# USB_HUB.net
KiCad netlist of a schematic drawn in Altium Designer
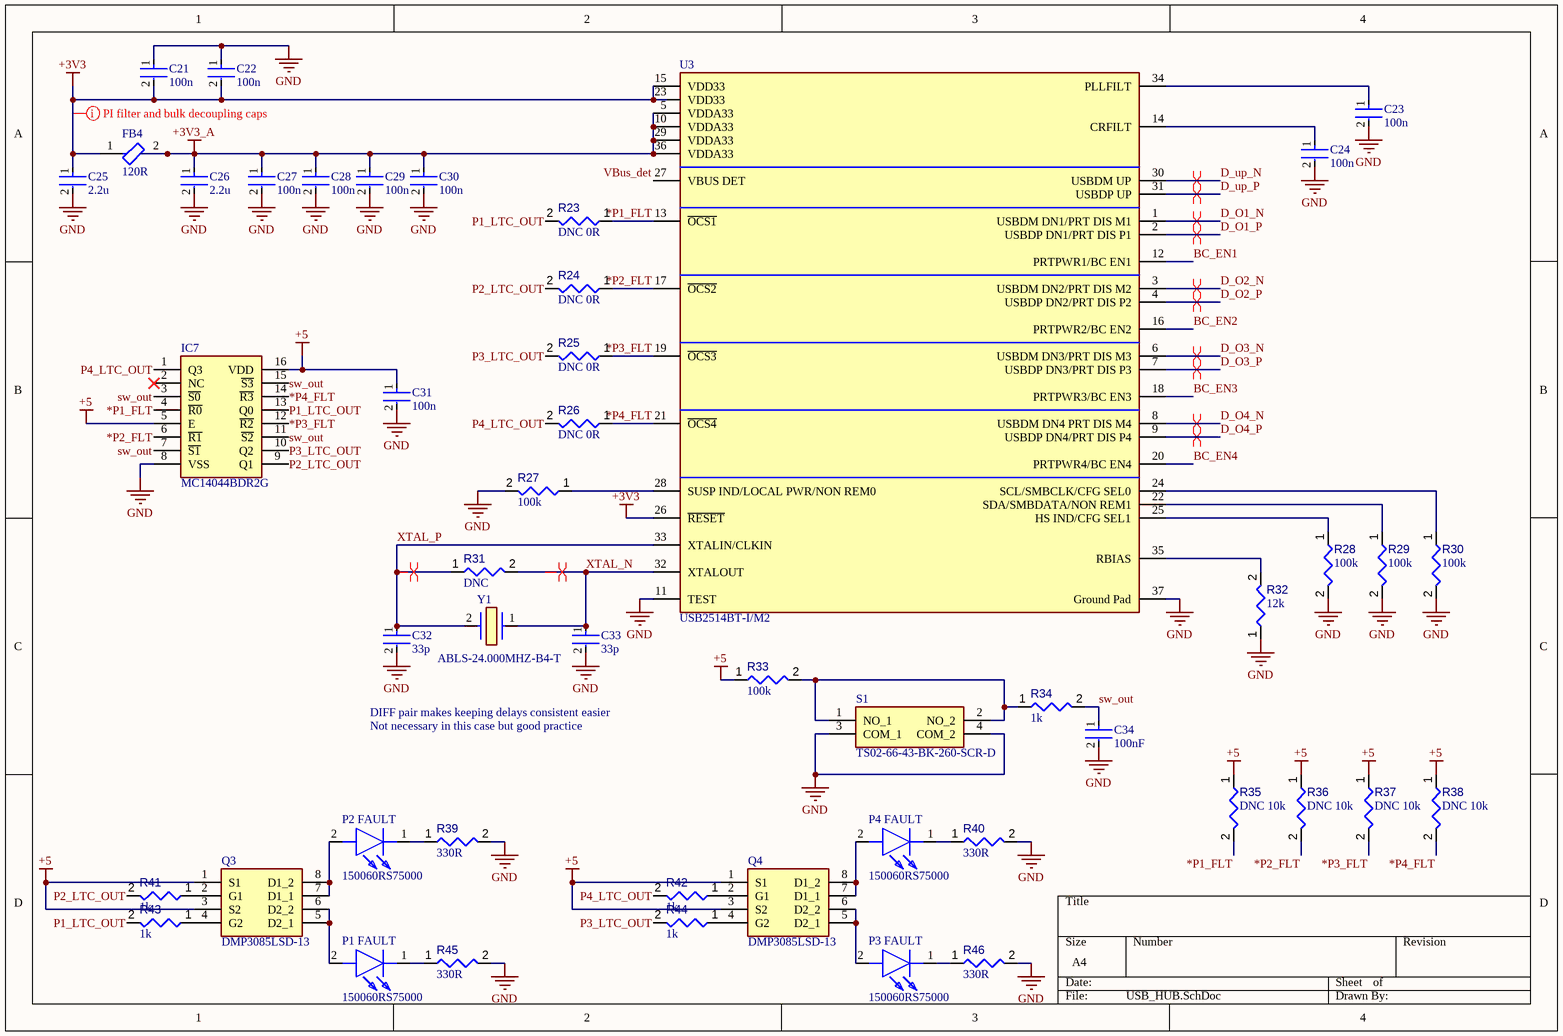
[diagram p0: USB_HUB.SchDoc]

(export (version "E")
  (design (tool "Eeschema 10.0.6"))
  (components
    (comp (ref "C21")
      (value "0603 CAP")
      (footprint "PCB1:0603-C")
      (fields
        (field (name "VOLTAGE") "6.3V")
        (field (name "TOLERANCE") "20%")
        (field (name "MANUFACTURER") "Murata")
        (field (name "CAPACITANCE") "100n")
      )
      (libsource (lib "Personal Library") (part "CMP-2006-02792-2"))
    )
    (comp (ref "C22")
      (value "0603 CAP")
      (footprint "PCB1:0603-C")
      (fields
        (field (name "VOLTAGE") "6.3V")
        (field (name "TOLERANCE") "20%")
        (field (name "MANUFACTURER") "Murata")
        (field (name "CAPACITANCE") "100n")
      )
      (libsource (lib "Personal Library") (part "CMP-2006-02792-2"))
    )
    (comp (ref "C23")
      (value "0603 CAP")
      (footprint "PCB1:0603-C")
      (fields
        (field (name "VOLTAGE") "6.3V")
        (field (name "TOLERANCE") "20%")
        (field (name "MANUFACTURER") "Murata")
        (field (name "CAPACITANCE") "100n")
      )
      (libsource (lib "Personal Library") (part "CMP-2006-02792-2"))
    )
    (comp (ref "C24")
      (value "0603 CAP")
      (footprint "PCB1:0603-C")
      (fields
        (field (name "VOLTAGE") "6.3V")
        (field (name "TOLERANCE") "20%")
        (field (name "MANUFACTURER") "Murata")
        (field (name "CAPACITANCE") "100n")
      )
      (libsource (lib "Personal Library") (part "CMP-2006-02792-2"))
    )
    (comp (ref "C25")
      (value "0603 CAP")
      (footprint "PCB1:0603-C")
      (fields
        (field (name "VOLTAGE") "6.3V")
        (field (name "TOLERANCE") "20%")
        (field (name "MANUFACTURER") "Murata")
        (field (name "CAPACITANCE") "2.2u")
      )
      (libsource (lib "Personal Library") (part "CMP-2006-02792-2"))
    )
    (comp (ref "C26")
      (value "0603 CAP")
      (footprint "PCB1:0603-C")
      (fields
        (field (name "VOLTAGE") "6.3V")
        (field (name "TOLERANCE") "20%")
        (field (name "MANUFACTURER") "Murata")
        (field (name "CAPACITANCE") "2.2u")
      )
      (libsource (lib "Personal Library") (part "CMP-2006-02792-2"))
    )
    (comp (ref "C27")
      (value "0603 CAP")
      (footprint "PCB1:0603-C")
      (fields
        (field (name "VOLTAGE") "6.3V")
        (field (name "TOLERANCE") "20%")
        (field (name "MANUFACTURER") "Murata")
        (field (name "CAPACITANCE") "100n")
      )
      (libsource (lib "Personal Library") (part "CMP-2006-02792-2"))
    )
    (comp (ref "C28")
      (value "0603 CAP")
      (footprint "PCB1:0603-C")
      (fields
        (field (name "VOLTAGE") "6.3V")
        (field (name "TOLERANCE") "20%")
        (field (name "MANUFACTURER") "Murata")
        (field (name "CAPACITANCE") "100n")
      )
      (libsource (lib "Personal Library") (part "CMP-2006-02792-2"))
    )
    (comp (ref "C29")
      (value "0603 CAP")
      (footprint "PCB1:0603-C")
      (fields
        (field (name "VOLTAGE") "6.3V")
        (field (name "TOLERANCE") "20%")
        (field (name "MANUFACTURER") "Murata")
        (field (name "CAPACITANCE") "100n")
      )
      (libsource (lib "Personal Library") (part "CMP-2006-02792-2"))
    )
    (comp (ref "C30")
      (value "0603 CAP")
      (footprint "PCB1:0603-C")
      (fields
        (field (name "VOLTAGE") "6.3V")
        (field (name "TOLERANCE") "20%")
        (field (name "MANUFACTURER") "Murata")
        (field (name "CAPACITANCE") "100n")
      )
      (libsource (lib "Personal Library") (part "CMP-2006-02792-2"))
    )
    (comp (ref "C31")
      (value "0603 CAP")
      (footprint "PCB1:0603-C")
      (fields
        (field (name "VOLTAGE") "6.3V")
        (field (name "TOLERANCE") "20%")
        (field (name "MANUFACTURER") "Murata")
        (field (name "CAPACITANCE") "100n")
      )
      (libsource (lib "Personal Library") (part "CMP-2006-02792-2"))
    )
    (comp (ref "C32")
      (value "0603 CAP")
      (footprint "PCB1:0603-C")
      (fields
        (field (name "VOLTAGE") "6.3V")
        (field (name "TOLERANCE") "20%")
        (field (name "MANUFACTURER") "Murata")
        (field (name "CAPACITANCE") "33p")
      )
      (libsource (lib "Personal Library") (part "CMP-2006-02792-2"))
    )
    (comp (ref "C33")
      (value "0603 CAP")
      (footprint "PCB1:0603-C")
      (fields
        (field (name "VOLTAGE") "6.3V")
        (field (name "TOLERANCE") "20%")
        (field (name "MANUFACTURER") "Murata")
        (field (name "CAPACITANCE") "33p")
      )
      (libsource (lib "Personal Library") (part "CMP-2006-02792-2"))
    )
    (comp (ref "C34")
      (value "100nF")
      (footprint "FP-GRM188-0_1-e0_2_0_55-IPC_A")
      (description "Chip Multilayer Ceramic Capacitors for General Purpose, 0603, 10uF, X5R, 15%, 20%, 6.3V")
      (fields (field (name "VOLTAGE") "6.3V") (field (name "TOLERANCE") "20%"))
      (libsource (lib "Altium Content Vault") (part "02cd4be3c70576c341d710602a673aa"))
    )
    (comp (ref "FB4")
      (value "120R")
      (footprint "FP-ILHB-0805-IPC_C")
      (description "FERRITE BEAD 600 OHM 0805 1LN")
      (fields
        (field (name "TOLERANCE") "25%")
        (field (name "OCTOPART") "https://octopart.com/ilhb0805er601v-vishay-39650184")
      )
      (libsource (lib "Altium Content Vault") (part "5f30dd21d616792df468990f7003faa"))
    )
    (comp (ref "IC7")
      (value "MC14044BDR2G")
      (footprint "SamacSys:SOIC127P600X175-16N")
      (description "Integrated Circuit")
      (fields (field (name "MOUSER PART NUMBER") "863-MC14044BDR2G"))
      (libsource (lib "*") (part "MC14044BDR2G"))
    )
    (comp (ref "P1 FAULT")
      (value "150060RS75000")
      (footprint "SamacSys:LEDC1608X80N")
      (description "LED")
      (fields (field (name "MOUSER PART NUMBER") "710-150060RS75000"))
      (libsource (lib "*") (part "150060RS75000"))
    )
    (comp (ref "P2 FAULT")
      (value "150060RS75000")
      (footprint "SamacSys:LEDC1608X80N")
      (description "LED")
      (fields (field (name "MOUSER PART NUMBER") "710-150060RS75000"))
      (libsource (lib "*") (part "150060RS75000"))
    )
    (comp (ref "P3 FAULT")
      (value "150060RS75000")
      (footprint "SamacSys:LEDC1608X80N")
      (description "LED")
      (fields (field (name "MOUSER PART NUMBER") "710-150060RS75000"))
      (libsource (lib "*") (part "150060RS75000"))
    )
    (comp (ref "P4 FAULT")
      (value "150060RS75000")
      (footprint "SamacSys:LEDC1608X80N")
      (description "LED")
      (fields (field (name "MOUSER PART NUMBER") "710-150060RS75000"))
      (libsource (lib "*") (part "150060RS75000"))
    )
    (comp (ref "Q3")
      (value "DMP3085LSD-13")
      (footprint "SamacSys:SOIC127P600X175-8N")
      (description "MOSFET (P-Channel)")
      (fields (field (name "MOUSER PART NUMBER") "621-DMP3085LSD-13"))
      (libsource (lib "Personal Library") (part "DMP3085LSD-13"))
    )
    (comp (ref "Q4")
      (value "DMP3085LSD-13")
      (footprint "SamacSys:SOIC127P600X175-8N")
      (description "MOSFET (P-Channel)")
      (fields (field (name "MOUSER PART NUMBER") "621-DMP3085LSD-13"))
      (libsource (lib "Personal Library") (part "DMP3085LSD-13"))
    )
    (comp (ref "R23")
      (value "DNC 0R")
      (footprint "PCB1:0603-R")
      (description "0603 Resistor")
      (fields (field (name "POWER") "100mW") (field (name "TOLERANCE") "1%"))
      (libsource (lib "Personal Library") (part "CMP-009-00014-5"))
    )
    (comp (ref "R24")
      (value "DNC 0R")
      (footprint "PCB1:0603-R")
      (description "0603 Resistor")
      (fields (field (name "POWER") "100mW") (field (name "TOLERANCE") "1%"))
      (libsource (lib "Personal Library") (part "CMP-009-00014-5"))
    )
    (comp (ref "R25")
      (value "DNC 0R")
      (footprint "PCB1:0603-R")
      (description "0603 Resistor")
      (fields (field (name "POWER") "100mW") (field (name "TOLERANCE") "1%"))
      (libsource (lib "Personal Library") (part "CMP-009-00014-5"))
    )
    (comp (ref "R26")
      (value "DNC 0R")
      (footprint "PCB1:0603-R")
      (description "0603 Resistor")
      (fields (field (name "POWER") "100mW") (field (name "TOLERANCE") "1%"))
      (libsource (lib "Personal Library") (part "CMP-009-00014-5"))
    )
    (comp (ref "R27")
      (value "100k")
      (footprint "PCB1:0603-R")
      (description "0603 Resistor")
      (fields (field (name "POWER") "100mW") (field (name "TOLERANCE") "1%"))
      (libsource (lib "Personal Library") (part "CMP-009-00014-5"))
    )
    (comp (ref "R28")
      (value "100k")
      (footprint "PCB1:0603-R")
      (description "0603 Resistor")
      (fields (field (name "POWER") "100mW") (field (name "TOLERANCE") "1%"))
      (libsource (lib "Personal Library") (part "CMP-009-00014-5"))
    )
    (comp (ref "R29")
      (value "100k")
      (footprint "PCB1:0603-R")
      (description "0603 Resistor")
      (fields (field (name "POWER") "100mW") (field (name "TOLERANCE") "1%"))
      (libsource (lib "Personal Library") (part "CMP-009-00014-5"))
    )
    (comp (ref "R30")
      (value "100k")
      (footprint "PCB1:0603-R")
      (description "0603 Resistor")
      (fields (field (name "POWER") "100mW") (field (name "TOLERANCE") "1%"))
      (libsource (lib "Personal Library") (part "CMP-009-00014-5"))
    )
    (comp (ref "R31")
      (value "DNC")
      (footprint "PCB1:0603-R")
      (description "0603 Resistor")
      (fields (field (name "POWER") "100mW") (field (name "TOLERANCE") "1%"))
      (libsource (lib "Personal Library") (part "CMP-009-00014-5"))
    )
    (comp (ref "R32")
      (value "12k")
      (footprint "PCB1:0603-R")
      (description "0603 Resistor +-1%")
      (fields (field (name "POWER") "100mW") (field (name "TOLERANCE") "1%"))
      (libsource (lib "Personal Library") (part "CMP-009-00014-5"))
    )
    (comp (ref "R33")
      (value "100k")
      (footprint "PCB1:0603-R")
      (description "0603 Resistor")
      (fields (field (name "POWER") "100mW") (field (name "TOLERANCE") "1%"))
      (libsource (lib "Personal Library") (part "CMP-009-00014-5"))
    )
    (comp (ref "R34")
      (value "1k")
      (footprint "PCB1:0603-R")
      (description "0603 Resistor")
      (fields (field (name "POWER") "100mW") (field (name "TOLERANCE") "1%"))
      (libsource (lib "Personal Library") (part "CMP-009-00014-5"))
    )
    (comp (ref "R35")
      (value "DNC 10k")
      (footprint "PCB1:0603-R")
      (description "0603 Resistor")
      (fields (field (name "POWER") "100mW") (field (name "TOLERANCE") "1%"))
      (libsource (lib "Personal Library") (part "CMP-009-00014-5"))
    )
    (comp (ref "R36")
      (value "DNC 10k")
      (footprint "PCB1:0603-R")
      (description "0603 Resistor")
      (fields (field (name "POWER") "100mW") (field (name "TOLERANCE") "1%"))
      (libsource (lib "Personal Library") (part "CMP-009-00014-5"))
    )
    (comp (ref "R37")
      (value "DNC 10k")
      (footprint "PCB1:0603-R")
      (description "0603 Resistor")
      (fields (field (name "POWER") "100mW") (field (name "TOLERANCE") "1%"))
      (libsource (lib "Personal Library") (part "CMP-009-00014-5"))
    )
    (comp (ref "R38")
      (value "DNC 10k")
      (footprint "PCB1:0603-R")
      (description "0603 Resistor")
      (fields (field (name "POWER") "100mW") (field (name "TOLERANCE") "1%"))
      (libsource (lib "Personal Library") (part "CMP-009-00014-5"))
    )
    (comp (ref "R39")
      (value "330R")
      (footprint "PCB1:0603-R")
      (description "0603 Resistor")
      (fields (field (name "POWER") "100mW") (field (name "TOLERANCE") "1%"))
      (libsource (lib "Personal Library") (part "CMP-009-00014-5"))
    )
    (comp (ref "R40")
      (value "330R")
      (footprint "PCB1:0603-R")
      (description "0603 Resistor")
      (fields (field (name "POWER") "100mW") (field (name "TOLERANCE") "1%"))
      (libsource (lib "Personal Library") (part "CMP-009-00014-5"))
    )
    (comp (ref "R41")
      (value "1k")
      (footprint "PCB1:0603-R")
      (description "0603 Resistor")
      (fields (field (name "POWER") "100mW") (field (name "TOLERANCE") "1%"))
      (libsource (lib "Personal Library") (part "CMP-009-00014-5"))
    )
    (comp (ref "R42")
      (value "1k")
      (footprint "PCB1:0603-R")
      (description "0603 Resistor")
      (fields (field (name "POWER") "100mW") (field (name "TOLERANCE") "1%"))
      (libsource (lib "Personal Library") (part "CMP-009-00014-5"))
    )
    (comp (ref "R43")
      (value "1k")
      (footprint "PCB1:0603-R")
      (description "0603 Resistor")
      (fields (field (name "POWER") "100mW") (field (name "TOLERANCE") "1%"))
      (libsource (lib "Personal Library") (part "CMP-009-00014-5"))
    )
    (comp (ref "R44")
      (value "1k")
      (footprint "PCB1:0603-R")
      (description "0603 Resistor")
      (fields (field (name "POWER") "100mW") (field (name "TOLERANCE") "1%"))
      (libsource (lib "Personal Library") (part "CMP-009-00014-5"))
    )
    (comp (ref "R45")
      (value "330R")
      (footprint "PCB1:0603-R")
      (description "0603 Resistor")
      (fields (field (name "POWER") "100mW") (field (name "TOLERANCE") "1%"))
      (libsource (lib "Personal Library") (part "CMP-009-00014-5"))
    )
    (comp (ref "R46")
      (value "330R")
      (footprint "PCB1:0603-R")
      (description "0603 Resistor")
      (fields (field (name "POWER") "100mW") (field (name "TOLERANCE") "1%"))
      (libsource (lib "Personal Library") (part "CMP-009-00014-5"))
    )
    (comp (ref "S1")
      (value "TS02-66-43-BK-260-SCR-D")
      (footprint "SamacSys:TS026643BK260SCRD")
      (description "Switch")
      (fields (field (name "MOUSER PART NUMBER") "179-TS026643BK260SCR"))
      (libsource (lib "*") (part "TS02-66-43-BK-260-SCR-D"))
    )
    (comp (ref "U3")
      (value "USB2514BT-I/M2")
      (footprint "FP-36SQFN-3706-6x6B-MFG")
      (description "IC HUB CTLR 4PORT USB 2.0 HS 36S")
      (libsource (lib "Altium Content Vault") (part "1fbfcce16c96605cc105739979cbbf3"))
    )
    (comp (ref "Y1")
      (value "ABLS-24.000MHZ-B4-T")
      (footprint "SamacSys:ABLS24000MHZB4T")
      (description "Crystal or Oscillator")
      (fields (field (name "MOUSER PART NUMBER") "815-ABLS-24.0M-T"))
      (libsource (lib "*") (part "ABLS-24.000MHZ-B4-T"))
    )
  )
  (nets
    (net (code "1") (name "+3V3") (class "Default")
      (node (ref "C21") (pin "2") (pinfunction "2_2") (pintype "passive"))
      (node (ref "C22") (pin "2") (pinfunction "2_2") (pintype "passive"))
      (node (ref "C25") (pin "1") (pinfunction "1_1") (pintype "passive"))
      (node (ref "FB4") (pin "1") (pinfunction "1_1") (pintype "passive"))
      (node (ref "U3") (pin "15") (pinfunction "VDD33_15") (pintype "passive"))
      (node (ref "U3") (pin "23") (pinfunction "VDD33_23") (pintype "passive"))
      (node (ref "U3") (pin "26") (pinfunction "~{RESET}_26") (pintype "passive"))
    )
    (net (code "2") (name "+3V3_A") (class "Default")
      (node (ref "C26") (pin "1") (pinfunction "1_1") (pintype "passive"))
      (node (ref "C27") (pin "1") (pinfunction "1_1") (pintype "passive"))
      (node (ref "C28") (pin "1") (pinfunction "1_1") (pintype "passive"))
      (node (ref "C29") (pin "1") (pinfunction "1_1") (pintype "passive"))
      (node (ref "C30") (pin "1") (pinfunction "1_1") (pintype "passive"))
      (node (ref "FB4") (pin "2") (pinfunction "2_2") (pintype "passive"))
      (node (ref "U3") (pin "10") (pinfunction "VDDA33_10") (pintype "passive"))
      (node (ref "U3") (pin "29") (pinfunction "VDDA33_29") (pintype "passive"))
      (node (ref "U3") (pin "36") (pinfunction "VDDA33_36") (pintype "passive"))
      (node (ref "U3") (pin "5") (pinfunction "VDDA33_5") (pintype "passive"))
    )
    (net (code "3") (name "+5") (class "Default")
      (node (ref "C31") (pin "1") (pinfunction "1_1") (pintype "passive"))
      (node (ref "IC7") (pin "16") (pinfunction "VDD_16") (pintype "passive"))
      (node (ref "IC7") (pin "5") (pinfunction "E_5") (pintype "passive"))
      (node (ref "Q3") (pin "1") (pinfunction "S1_1") (pintype "passive"))
      (node (ref "Q3") (pin "3") (pinfunction "S2_3") (pintype "passive"))
      (node (ref "Q4") (pin "1") (pinfunction "S1_1") (pintype "passive"))
      (node (ref "Q4") (pin "3") (pinfunction "S2_3") (pintype "passive"))
      (node (ref "R33") (pin "1") (pinfunction "1_1") (pintype "passive"))
      (node (ref "R35") (pin "1") (pinfunction "1_1") (pintype "passive"))
      (node (ref "R36") (pin "1") (pinfunction "1_1") (pintype "passive"))
      (node (ref "R37") (pin "1") (pinfunction "1_1") (pintype "passive"))
      (node (ref "R38") (pin "1") (pinfunction "1_1") (pintype "passive"))
    )
    (net (code "4") (name "/*P1_FLT") (class "Default")
      (node (ref "IC7") (pin "4") (pinfunction "~{R0}_4") (pintype "passive"))
      (node (ref "R23") (pin "1") (pinfunction "1_1") (pintype "passive"))
      (node (ref "R35") (pin "2") (pinfunction "2_2") (pintype "passive"))
      (node (ref "U3") (pin "13") (pinfunction "~{OCS1}_13") (pintype "passive"))
    )
    (net (code "5") (name "/*P2_FLT") (class "Default")
      (node (ref "IC7") (pin "6") (pinfunction "~{R1}_6") (pintype "passive"))
      (node (ref "R24") (pin "1") (pinfunction "1_1") (pintype "passive"))
      (node (ref "R36") (pin "2") (pinfunction "2_2") (pintype "passive"))
      (node (ref "U3") (pin "17") (pinfunction "~{OCS2}_17") (pintype "passive"))
    )
    (net (code "6") (name "/*P3_FLT") (class "Default")
      (node (ref "IC7") (pin "12") (pinfunction "~{R2}_12") (pintype "passive"))
      (node (ref "R25") (pin "1") (pinfunction "1_1") (pintype "passive"))
      (node (ref "R37") (pin "2") (pinfunction "2_2") (pintype "passive"))
      (node (ref "U3") (pin "19") (pinfunction "~{OCS3}_19") (pintype "passive"))
    )
    (net (code "7") (name "/*P4_FLT") (class "Default")
      (node (ref "IC7") (pin "14") (pinfunction "~{R3}_14") (pintype "passive"))
      (node (ref "R26") (pin "1") (pinfunction "1_1") (pintype "passive"))
      (node (ref "R38") (pin "2") (pinfunction "2_2") (pintype "passive"))
      (node (ref "U3") (pin "21") (pinfunction "~{OCS4}_21") (pintype "passive"))
    )
    (net (code "8") (name "/BC_EN1") (class "Default")
      (node (ref "U3") (pin "12") (pinfunction "PRTPWR1/BC_EN1_12") (pintype "passive"))
    )
    (net (code "9") (name "/BC_EN2") (class "Default")
      (node (ref "U3") (pin "16") (pinfunction "PRTPWR2/BC_EN2_16") (pintype "passive"))
    )
    (net (code "10") (name "/BC_EN3") (class "Default")
      (node (ref "U3") (pin "18") (pinfunction "PRTPWR3/BC_EN3_18") (pintype "passive"))
    )
    (net (code "11") (name "/BC_EN4") (class "Default")
      (node (ref "U3") (pin "20") (pinfunction "PRTPWR4/BC_EN4_20") (pintype "passive"))
    )
    (net (code "12") (name "/D_O1_N") (class "Default")
      (node (ref "U3") (pin "1") (pinfunction "USBDM_DN1/PRT_DIS_M1_1") (pintype "passive"))
    )
    (net (code "13") (name "/D_O1_P") (class "Default")
      (node (ref "U3") (pin "2") (pinfunction "USBDP_DN1/PRT_DIS_P1_2") (pintype "passive"))
    )
    (net (code "14") (name "/D_O2_N") (class "Default")
      (node (ref "U3") (pin "3") (pinfunction "USBDM_DN2/PRT_DIS_M2_3") (pintype "passive"))
    )
    (net (code "15") (name "/D_O2_P") (class "Default")
      (node (ref "U3") (pin "4") (pinfunction "USBDP_DN2/PRT_DIS_P2_4") (pintype "passive"))
    )
    (net (code "16") (name "/D_O3_N") (class "Default")
      (node (ref "U3") (pin "6") (pinfunction "USBDM_DN3/PRT_DIS_M3_6") (pintype "passive"))
    )
    (net (code "17") (name "/D_O3_P") (class "Default")
      (node (ref "U3") (pin "7") (pinfunction "USBDP_DN3/PRT_DIS_P3_7") (pintype "passive"))
    )
    (net (code "18") (name "/D_O4_N") (class "Default")
      (node (ref "U3") (pin "8") (pinfunction "USBDM_DN4_PRT_DIS_M4_8") (pintype "passive"))
    )
    (net (code "19") (name "/D_O4_P") (class "Default")
      (node (ref "U3") (pin "9") (pinfunction "USBDP_DN4/PRT_DIS_P4_9") (pintype "passive"))
    )
    (net (code "20") (name "/D_up_N") (class "Default")
      (node (ref "U3") (pin "30") (pinfunction "USBDM_UP_30") (pintype "passive"))
    )
    (net (code "21") (name "/D_up_P") (class "Default")
      (node (ref "U3") (pin "31") (pinfunction "USBDP_UP_31") (pintype "passive"))
    )
    (net (code "22") (name "/P1_LTC_OUT") (class "Default")
      (node (ref "IC7") (pin "13") (pinfunction "Q0_13") (pintype "passive"))
      (node (ref "R23") (pin "2") (pinfunction "2_2") (pintype "passive"))
      (node (ref "R43") (pin "2") (pinfunction "2_2") (pintype "passive"))
    )
    (net (code "23") (name "/P2_LTC_OUT") (class "Default")
      (node (ref "IC7") (pin "9") (pinfunction "Q1_9") (pintype "passive"))
      (node (ref "R24") (pin "2") (pinfunction "2_2") (pintype "passive"))
      (node (ref "R41") (pin "2") (pinfunction "2_2") (pintype "passive"))
    )
    (net (code "24") (name "/P3_LTC_OUT") (class "Default")
      (node (ref "IC7") (pin "10") (pinfunction "Q2_10") (pintype "passive"))
      (node (ref "R25") (pin "2") (pinfunction "2_2") (pintype "passive"))
      (node (ref "R44") (pin "2") (pinfunction "2_2") (pintype "passive"))
    )
    (net (code "25") (name "/P4_LTC_OUT") (class "Default")
      (node (ref "IC7") (pin "1") (pinfunction "Q3_1") (pintype "passive"))
      (node (ref "R26") (pin "2") (pinfunction "2_2") (pintype "passive"))
      (node (ref "R42") (pin "2") (pinfunction "2_2") (pintype "passive"))
    )
    (net (code "26") (name "/VBus_det") (class "Default")
      (node (ref "U3") (pin "27") (pinfunction "VBUS_DET_27") (pintype "passive"))
    )
    (net (code "27") (name "/XTAL_N") (class "Default")
      (node (ref "C33") (pin "1") (pinfunction "1_1") (pintype "passive"))
      (node (ref "R31") (pin "2") (pinfunction "2_2") (pintype "passive"))
      (node (ref "U3") (pin "32") (pinfunction "XTALOUT_32") (pintype "passive"))
      (node (ref "Y1") (pin "1") (pinfunction "CRYSTAL_1_1") (pintype "passive"))
    )
    (net (code "28") (name "/XTAL_P") (class "Default")
      (node (ref "C32") (pin "1") (pinfunction "1_1") (pintype "passive"))
      (node (ref "R31") (pin "1") (pinfunction "1_1") (pintype "passive"))
      (node (ref "U3") (pin "33") (pinfunction "XTALIN/CLKIN_33") (pintype "passive"))
      (node (ref "Y1") (pin "2") (pinfunction "CRYSTAL_2_2") (pintype "passive"))
    )
    (net (code "29") (name "/sw_out") (class "Default")
      (node (ref "C34") (pin "1") (pinfunction "1_1") (pintype "passive"))
      (node (ref "IC7") (pin "11") (pinfunction "~{S2}_11") (pintype "passive"))
      (node (ref "IC7") (pin "15") (pinfunction "~{S3}_15") (pintype "passive"))
      (node (ref "IC7") (pin "3") (pinfunction "~{S0}_3") (pintype "passive"))
      (node (ref "IC7") (pin "7") (pinfunction "~{S1}_7") (pintype "passive"))
      (node (ref "R34") (pin "2") (pinfunction "2_2") (pintype "passive"))
    )
    (net (code "30") (name "GND") (class "Default")
      (node (ref "C21") (pin "1") (pinfunction "1_1") (pintype "passive"))
      (node (ref "C22") (pin "1") (pinfunction "1_1") (pintype "passive"))
      (node (ref "C23") (pin "2") (pinfunction "2_2") (pintype "passive"))
      (node (ref "C24") (pin "2") (pinfunction "2_2") (pintype "passive"))
      (node (ref "C25") (pin "2") (pinfunction "2_2") (pintype "passive"))
      (node (ref "C26") (pin "2") (pinfunction "2_2") (pintype "passive"))
      (node (ref "C27") (pin "2") (pinfunction "2_2") (pintype "passive"))
      (node (ref "C28") (pin "2") (pinfunction "2_2") (pintype "passive"))
      (node (ref "C29") (pin "2") (pinfunction "2_2") (pintype "passive"))
      (node (ref "C30") (pin "2") (pinfunction "2_2") (pintype "passive"))
      (node (ref "C31") (pin "2") (pinfunction "2_2") (pintype "passive"))
      (node (ref "C32") (pin "2") (pinfunction "2_2") (pintype "passive"))
      (node (ref "C33") (pin "2") (pinfunction "2_2") (pintype "passive"))
      (node (ref "C34") (pin "2") (pinfunction "2_2") (pintype "passive"))
      (node (ref "IC7") (pin "8") (pinfunction "VSS_8") (pintype "passive"))
      (node (ref "R27") (pin "2") (pinfunction "2_2") (pintype "passive"))
      (node (ref "R28") (pin "2") (pinfunction "2_2") (pintype "passive"))
      (node (ref "R29") (pin "2") (pinfunction "2_2") (pintype "passive"))
      (node (ref "R30") (pin "2") (pinfunction "2_2") (pintype "passive"))
      (node (ref "R32") (pin "1") (pinfunction "1_1") (pintype "passive"))
      (node (ref "R39") (pin "2") (pinfunction "2_2") (pintype "passive"))
      (node (ref "R40") (pin "2") (pinfunction "2_2") (pintype "passive"))
      (node (ref "R45") (pin "2") (pinfunction "2_2") (pintype "passive"))
      (node (ref "R46") (pin "2") (pinfunction "2_2") (pintype "passive"))
      (node (ref "S1") (pin "3") (pinfunction "COM_1_3") (pintype "passive"))
      (node (ref "S1") (pin "4") (pinfunction "COM_2_4") (pintype "passive"))
      (node (ref "U3") (pin "11") (pinfunction "TEST_11") (pintype "passive"))
      (node (ref "U3") (pin "37") (pinfunction "Ground_Pad_37") (pintype "passive"))
    )
    (net (code "31") (name "Net-(P1 FAULT-A)") (class "Default")
      (node (ref "P1 FAULT") (pin "2") (pinfunction "A_2") (pintype "passive"))
      (node (ref "Q3") (pin "5") (pinfunction "D2_1_5") (pintype "passive"))
      (node (ref "Q3") (pin "6") (pinfunction "D2_2_6") (pintype "passive"))
    )
    (net (code "32") (name "Net-(P1 FAULT-K)") (class "Default")
      (node (ref "P1 FAULT") (pin "1") (pinfunction "K_1") (pintype "passive"))
      (node (ref "R45") (pin "1") (pinfunction "1_1") (pintype "passive"))
    )
    (net (code "33") (name "Net-(P2 FAULT-A)") (class "Default")
      (node (ref "P2 FAULT") (pin "2") (pinfunction "A_2") (pintype "passive"))
      (node (ref "Q3") (pin "7") (pinfunction "D1_1_7") (pintype "passive"))
      (node (ref "Q3") (pin "8") (pinfunction "D1_2_8") (pintype "passive"))
    )
    (net (code "34") (name "Net-(P2 FAULT-K)") (class "Default")
      (node (ref "P2 FAULT") (pin "1") (pinfunction "K_1") (pintype "passive"))
      (node (ref "R39") (pin "1") (pinfunction "1_1") (pintype "passive"))
    )
    (net (code "35") (name "Net-(P3 FAULT-A)") (class "Default")
      (node (ref "P3 FAULT") (pin "2") (pinfunction "A_2") (pintype "passive"))
      (node (ref "Q4") (pin "5") (pinfunction "D2_1_5") (pintype "passive"))
      (node (ref "Q4") (pin "6") (pinfunction "D2_2_6") (pintype "passive"))
    )
    (net (code "36") (name "Net-(P3 FAULT-K)") (class "Default")
      (node (ref "P3 FAULT") (pin "1") (pinfunction "K_1") (pintype "passive"))
      (node (ref "R46") (pin "1") (pinfunction "1_1") (pintype "passive"))
    )
    (net (code "37") (name "Net-(P4 FAULT-A)") (class "Default")
      (node (ref "P4 FAULT") (pin "2") (pinfunction "A_2") (pintype "passive"))
      (node (ref "Q4") (pin "7") (pinfunction "D1_1_7") (pintype "passive"))
      (node (ref "Q4") (pin "8") (pinfunction "D1_2_8") (pintype "passive"))
    )
    (net (code "38") (name "Net-(P4 FAULT-K)") (class "Default")
      (node (ref "P4 FAULT") (pin "1") (pinfunction "K_1") (pintype "passive"))
      (node (ref "R40") (pin "1") (pinfunction "1_1") (pintype "passive"))
    )
    (net (code "39") (name "Net-(Q3-G1)") (class "Default")
      (node (ref "Q3") (pin "2") (pinfunction "G1_2") (pintype "passive"))
      (node (ref "R41") (pin "1") (pinfunction "1_1") (pintype "passive"))
    )
    (net (code "40") (name "Net-(Q3-G2)") (class "Default")
      (node (ref "Q3") (pin "4") (pinfunction "G2_4") (pintype "passive"))
      (node (ref "R43") (pin "1") (pinfunction "1_1") (pintype "passive"))
    )
    (net (code "41") (name "Net-(Q4-G1)") (class "Default")
      (node (ref "Q4") (pin "2") (pinfunction "G1_2") (pintype "passive"))
      (node (ref "R42") (pin "1") (pinfunction "1_1") (pintype "passive"))
    )
    (net (code "42") (name "Net-(Q4-G2)") (class "Default")
      (node (ref "Q4") (pin "4") (pinfunction "G2_4") (pintype "passive"))
      (node (ref "R44") (pin "1") (pinfunction "1_1") (pintype "passive"))
    )
    (net (code "43") (name "Net-(S1-NO_1)") (class "Default")
      (node (ref "R33") (pin "2") (pinfunction "2_2") (pintype "passive"))
      (node (ref "R34") (pin "1") (pinfunction "1_1") (pintype "passive"))
      (node (ref "S1") (pin "1") (pinfunction "NO_1_1") (pintype "passive"))
      (node (ref "S1") (pin "2") (pinfunction "NO_2_2") (pintype "passive"))
    )
    (net (code "44") (name "Net-(U3-CRFILT)") (class "Default")
      (node (ref "C24") (pin "1") (pinfunction "1_1") (pintype "passive"))
      (node (ref "U3") (pin "14") (pinfunction "CRFILT_14") (pintype "passive"))
    )
    (net (code "45") (name "Net-(U3-HS_IND{slash}CFG_SEL1)") (class "Default")
      (node (ref "R28") (pin "1") (pinfunction "1_1") (pintype "passive"))
      (node (ref "U3") (pin "25") (pinfunction "HS_IND/CFG_SEL1_25") (pintype "passive"))
    )
    (net (code "46") (name "Net-(U3-PLLFILT)") (class "Default")
      (node (ref "C23") (pin "1") (pinfunction "1_1") (pintype "passive"))
      (node (ref "U3") (pin "34") (pinfunction "PLLFILT_34") (pintype "passive"))
    )
    (net (code "47") (name "Net-(U3-RBIAS)") (class "Default")
      (node (ref "R32") (pin "2") (pinfunction "2_2") (pintype "passive"))
      (node (ref "U3") (pin "35") (pinfunction "RBIAS_35") (pintype "passive"))
    )
    (net (code "48") (name "Net-(U3-SCL{slash}SMBCLK{slash}CFG_SEL0)") (class "Default")
      (node (ref "R30") (pin "1") (pinfunction "1_1") (pintype "passive"))
      (node (ref "U3") (pin "24") (pinfunction "SCL/SMBCLK/CFG_SEL0_24") (pintype "passive"))
    )
    (net (code "49") (name "Net-(U3-SDA{slash}SMBDATA{slash}NON_REM1)") (class "Default")
      (node (ref "R29") (pin "1") (pinfunction "1_1") (pintype "passive"))
      (node (ref "U3") (pin "22") (pinfunction "SDA/SMBDATA/NON_REM1_22") (pintype "passive"))
    )
    (net (code "50") (name "Net-(U3-SUSP_IND{slash}LOCAL_PWR{slash}NON_REM0)") (class "Default")
      (node (ref "R27") (pin "1") (pinfunction "1_1") (pintype "passive"))
      (node (ref "U3") (pin "28") (pinfunction "SUSP_IND/LOCAL_PWR/NON_REM0_28") (pintype "passive"))
    )
    (net (code "51") (name "unconnected-(IC7-NC-Pad2)") (class "Default")
      (node (ref "IC7") (pin "2") (pinfunction "NC_2") (pintype "passive+no_connect"))
    )
  )
)
